# Audio_Output.net
KiCad netlist of a schematic drawn in Altium Designer
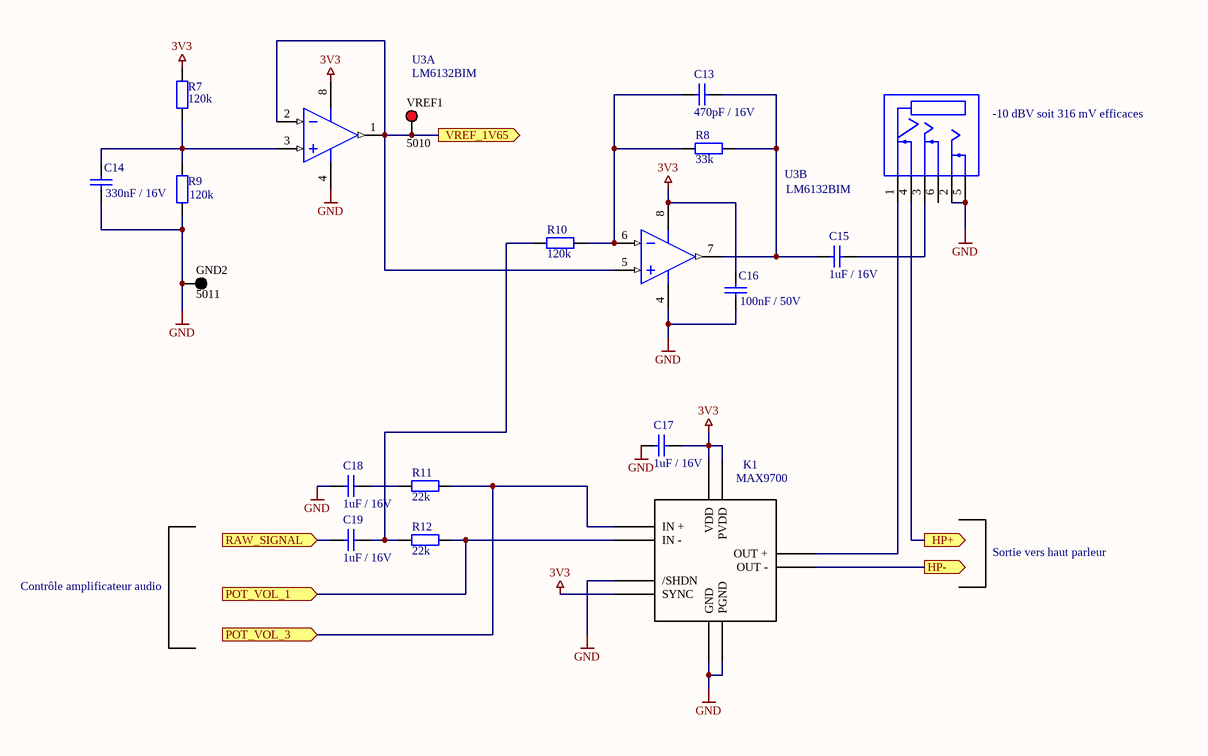
[diagram p0: Audio_Output.SchDoc]

(export (version "E")
  (design (tool "Eeschema 10.0.6"))
  (components
    (comp (ref "C13")
      (value "470pF / 16V")
      (footprint "CAPC0805")
      (description "Capacitor")
      (fields (field (name "PUBLISHER") "Altium Limited"))
      (libsource (lib "Miscellaneous Devices") (part "Cap"))
    )
    (comp (ref "C14")
      (value "330nF / 16V")
      (footprint "CAPC0805")
      (description "Capacitor")
      (fields (field (name "PUBLISHER") "Altium Limited"))
      (libsource (lib "Miscellaneous Devices") (part "Cap"))
    )
    (comp (ref "C15")
      (value "1uF / 16V")
      (footprint "CAPC0805")
      (description "Capacitor")
      (fields (field (name "PUBLISHER") "Altium Limited"))
      (libsource (lib "Miscellaneous Devices") (part "Cap"))
    )
    (comp (ref "C16")
      (value "100nF / 50V")
      (footprint "CAPC0805")
      (description "Capacitor")
      (fields (field (name "PUBLISHER") "Altium Limited"))
      (libsource (lib "Miscellaneous Devices") (part "Cap"))
    )
    (comp (ref "C17")
      (value "1uF / 16V")
      (footprint "CAPC0805")
      (description "Capacitor")
      (fields (field (name "PUBLISHER") "Altium Limited"))
      (libsource (lib "Miscellaneous Devices") (part "Cap"))
    )
    (comp (ref "C18")
      (value "1uF / 16V")
      (footprint "CAPC0805")
      (description "Capacitor")
      (fields (field (name "PUBLISHER") "Altium Limited"))
      (libsource (lib "Miscellaneous Devices") (part "Cap"))
    )
    (comp (ref "C19")
      (value "1uF / 16V")
      (footprint "CAPC0805")
      (description "Capacitor")
      (fields (field (name "PUBLISHER") "Altium Limited"))
      (libsource (lib "Miscellaneous Devices") (part "Cap"))
    )
    (comp (ref "GND2")
      (value "5011")
      (footprint "KSTN-5011_V")
      (description "Test Point, Black, Through Hole, RoHS, Bulk")
      (fields (field (name "MANUFACTURER") "Keystone"))
      (libsource (lib "Altium Content Vault") (part "TESTPOINT_BLACK"))
    )
    (comp (ref "J4")
      (value "SJ-63073E")
      (footprint "CUI_SJ-63073E")
      (description "Audio/RCA Connector")
      (fields
        (field (name "MF") "CUI Devices")
        (field (name "BUYPART") "https://www.snapeda.com/parts/SJ-63073E/CUI%20Devices/view-part/4973947/?ref=eda")
      )
      (libsource (lib "SJ-63073E") (part "SJ-63073E"))
    )
    (comp (ref "K1")
      (value "MAX9700")
      (footprint "SOP50P490X110-10N")
      (libsource (lib "MAX9700") (part "MAX9700"))
    )
    (comp (ref "R7")
      (value "120k")
      (footprint "RESC0805")
      (description "Resistor")
      (libsource (lib "") (part "RES_1"))
    )
    (comp (ref "R8")
      (value "33k")
      (footprint "RESC0805")
      (description "Resistor")
      (libsource (lib "Support_BAT_1043") (part "RES"))
    )
    (comp (ref "R9")
      (value "120k")
      (footprint "RESC0805")
      (description "Resistor")
      (libsource (lib "") (part "RES_1"))
    )
    (comp (ref "R10")
      (value "120k")
      (footprint "RESC0805")
      (description "Resistor")
      (libsource (lib "Support_BAT_1043") (part "RES"))
    )
    (comp (ref "R11")
      (value "22k")
      (footprint "RESC0805")
      (description "Resistor")
      (libsource (lib "Support_BAT_1043") (part "RES"))
    )
    (comp (ref "R12")
      (value "22k")
      (footprint "RESC0805")
      (description "Resistor")
      (libsource (lib "Support_BAT_1043") (part "RES"))
    )
    (comp (ref "U3")
      (value "LM6132BIM")
      (footprint "D0008A_N")
      (description "Dual Low Power 10 MHz Rail-to-Rail I/O Operational Amplifier, 8-pin Narrow SOIC")
      (fields (field (name "MANUFACTURER") "Texas Instruments"))
      (libsource (lib "Altium Content Vault") (part "AMP-OPA-LM6132-8"))
    )
    (comp (ref "VREF1")
      (value "5010")
      (footprint "KSTN-5010_V")
      (description "Test Point, Red, Through Hole, RoHS, Bulk")
      (fields (field (name "MANUFACTURER") "Keystone"))
      (libsource (lib "Altium Content Vault") (part "TESTPOINT_RED"))
    )
  )
  (nets
    (net (code "1") (name "/HP+") (class "Default")
      (node (ref "J4") (pin "4") (pinfunction "SLEEVE_SWITCH_4") (pintype "passive"))
    )
    (net (code "2") (name "/HP-") (class "Default")
      (node (ref "K1") (pin "9") (pinfunction "OUT_-_9") (pintype "passive"))
    )
    (net (code "3") (name "/POT_VOL_1") (class "Default")
      (node (ref "K1") (pin "3") (pinfunction "IN_-_3") (pintype "passive"))
      (node (ref "R12") (pin "1") (pinfunction "1_1") (pintype "passive"))
    )
    (net (code "4") (name "/POT_VOL_3") (class "Default")
      (node (ref "K1") (pin "2") (pinfunction "IN_+_2") (pintype "passive"))
      (node (ref "R11") (pin "1") (pinfunction "1_1") (pintype "passive"))
    )
    (net (code "5") (name "/RAW_SIGNAL") (class "Default")
      (node (ref "C19") (pin "2") (pinfunction "2_2") (pintype "passive"))
    )
    (net (code "6") (name "/VREF_1V65") (class "Default")
      (node (ref "U3") (pin "1") (pinfunction "OUTA_1") (pintype "output"))
      (node (ref "U3") (pin "2") (pinfunction "INA-_2") (pintype "input"))
      (node (ref "U3") (pin "5") (pinfunction "INB+_5") (pintype "input"))
      (node (ref "VREF1") (pin "1") (pinfunction "1_1") (pintype "passive"))
    )
    (net (code "7") (name "3V3") (class "Default")
      (node (ref "C16") (pin "2") (pinfunction "2_2") (pintype "passive"))
      (node (ref "C17") (pin "2") (pinfunction "2_2") (pintype "passive"))
      (node (ref "K1") (pin "1") (pinfunction "VDD_1") (pintype "passive"))
      (node (ref "K1") (pin "10") (pinfunction "PVDD_10") (pintype "passive"))
      (node (ref "K1") (pin "6") (pinfunction "SYNC_6") (pintype "passive"))
      (node (ref "R7") (pin "2") (pinfunction "2_2") (pintype "passive"))
      (node (ref "U3") (pin "8") (pinfunction "V+_8") (pintype "power_in"))
    )
    (net (code "8") (name "GND") (class "Default")
      (node (ref "C14") (pin "1") (pinfunction "1_1") (pintype "passive"))
      (node (ref "C16") (pin "1") (pinfunction "1_1") (pintype "passive"))
      (node (ref "C17") (pin "1") (pinfunction "1_1") (pintype "passive"))
      (node (ref "C18") (pin "1") (pinfunction "1_1") (pintype "passive"))
      (node (ref "GND2") (pin "1") (pinfunction "1_1") (pintype "passive"))
      (node (ref "J4") (pin "2") (pinfunction "TIP_2") (pintype "passive"))
      (node (ref "J4") (pin "5") (pinfunction "TIP_SWITCH_5") (pintype "passive"))
      (node (ref "K1") (pin "4") (pinfunction "GND_4") (pintype "passive"))
      (node (ref "K1") (pin "5") (pinfunction "/SHDN_5") (pintype "passive"))
      (node (ref "K1") (pin "7") (pinfunction "PGND_7") (pintype "passive"))
      (node (ref "R9") (pin "1") (pinfunction "1_1") (pintype "passive"))
      (node (ref "U3") (pin "4") (pinfunction "V-_4") (pintype "power_in"))
    )
    (net (code "9") (name "Net-(C18-Pad2)") (class "Default")
      (node (ref "C18") (pin "2") (pinfunction "2_2") (pintype "passive"))
      (node (ref "R11") (pin "2") (pinfunction "2_2") (pintype "passive"))
    )
    (net (code "10") (name "Net-(C19-Pad1)") (class "Default")
      (node (ref "C19") (pin "1") (pinfunction "1_1") (pintype "passive"))
      (node (ref "R10") (pin "2") (pinfunction "2_2") (pintype "passive"))
      (node (ref "R12") (pin "2") (pinfunction "2_2") (pintype "passive"))
    )
    (net (code "11") (name "Net-(J4-RING)") (class "Default")
      (node (ref "C15") (pin "1") (pinfunction "1_1") (pintype "passive"))
      (node (ref "J4") (pin "3") (pinfunction "RING_3") (pintype "passive"))
    )
    (net (code "12") (name "Net-(J4-SLEEVE)") (class "Default")
      (node (ref "J4") (pin "1") (pinfunction "SLEEVE_1") (pintype "passive"))
      (node (ref "K1") (pin "8") (pinfunction "OUT_+_8") (pintype "passive"))
    )
    (net (code "13") (name "Net-(U3A-INA+)") (class "Default")
      (node (ref "C14") (pin "2") (pinfunction "2_2") (pintype "passive"))
      (node (ref "R7") (pin "1") (pinfunction "1_1") (pintype "passive"))
      (node (ref "R9") (pin "2") (pinfunction "2_2") (pintype "passive"))
      (node (ref "U3") (pin "3") (pinfunction "INA+_3") (pintype "input"))
    )
    (net (code "14") (name "Net-(U3B-INB-)") (class "Default")
      (node (ref "C13") (pin "2") (pinfunction "2_2") (pintype "passive"))
      (node (ref "R10") (pin "1") (pinfunction "1_1") (pintype "passive"))
      (node (ref "R8") (pin "2") (pinfunction "2_2") (pintype "passive"))
      (node (ref "U3") (pin "6") (pinfunction "INB-_6") (pintype "input"))
    )
    (net (code "15") (name "Net-(U3B-OUTB)") (class "Default")
      (node (ref "C13") (pin "1") (pinfunction "1_1") (pintype "passive"))
      (node (ref "C15") (pin "2") (pinfunction "2_2") (pintype "passive"))
      (node (ref "R8") (pin "1") (pinfunction "1_1") (pintype "passive"))
      (node (ref "U3") (pin "7") (pinfunction "OUTB_7") (pintype "output"))
    )
    (net (code "16") (name "unconnected-(J4-RING_SWITCH-Pad6)") (class "Default")
      (node (ref "J4") (pin "6") (pinfunction "RING_SWITCH_6") (pintype "passive"))
    )
  )
)
